# metiumacs2.net
KiCad netlist of a schematic drawn in EAGLE
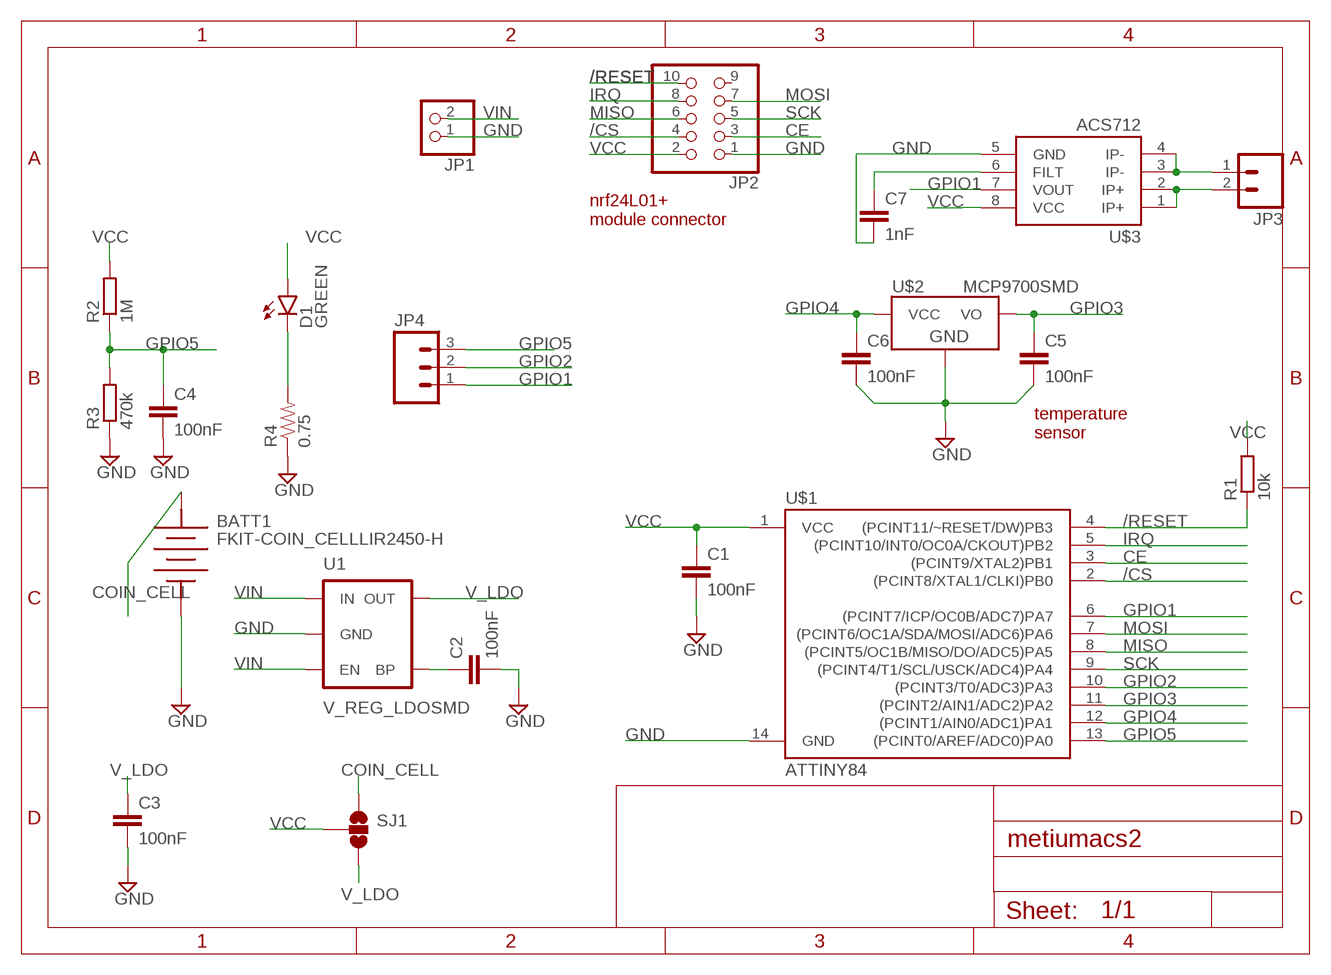
[diagram p0: schematic, sheet 1]

(export (version "E")
  (design (tool "Eeschema 10.0.6"))
  (components
    (comp (ref "BATT1")
      (value "FKIT-COIN_CELLLIR2450-H")
      (footprint "eagle-import:FKIT-LIR2450-H")
      (libsource (lib "eagle-import") (part "FKIT-COIN_CELLLIR2450-H"))
    )
    (comp (ref "C1")
      (value "100nF")
      (footprint "eagle-import:C0805")
      (libsource (lib "eagle-import") (part "C-EUC0805"))
    )
    (comp (ref "C2")
      (value "100nF")
      (footprint "eagle-import:C0805")
      (libsource (lib "eagle-import") (part "C-EUC0805"))
    )
    (comp (ref "C3")
      (value "100nF")
      (footprint "eagle-import:C0805")
      (libsource (lib "eagle-import") (part "C-EUC0805"))
    )
    (comp (ref "C4")
      (value "100nF")
      (footprint "eagle-import:C0805")
      (libsource (lib "eagle-import") (part "C-EUC0805"))
    )
    (comp (ref "C5")
      (value "100nF")
      (footprint "eagle-import:C0805")
      (libsource (lib "eagle-import") (part "C-EUC0805"))
    )
    (comp (ref "C6")
      (value "100nF")
      (footprint "eagle-import:C0805")
      (libsource (lib "eagle-import") (part "C-EUC0805"))
    )
    (comp (ref "C7")
      (value "1nF")
      (footprint "eagle-import:0603-CAP")
      (libsource (lib "eagle-import") (part "1NF/1000PF-50V-10%(0603)"))
    )
    (comp (ref "D1")
      (value "GREEN")
      (footprint "eagle-import:LED-0603")
      (libsource (lib "eagle-import") (part "LED-GREEN0603"))
    )
    (comp (ref "JP1")
      (value "HEADER-1X2ROUND")
      (footprint "eagle-import:1X02_ROUND")
      (libsource (lib "eagle-import") (part "HEADER-1X2ROUND"))
    )
    (comp (ref "JP2")
      (value "PINHD-2X5")
      (footprint "eagle-import:2X05M")
      (libsource (lib "eagle-import") (part "PINHD-2X5"))
    )
    (comp (ref "JP3")
      (value "M02PTH4")
      (footprint "eagle-import:1X02_XTRA_BIG")
      (libsource (lib "eagle-import") (part "M02PTH4"))
    )
    (comp (ref "JP4")
      (value "M03LONGPADS")
      (footprint "eagle-import:1X03_LONGPADS")
      (libsource (lib "eagle-import") (part "M03LONGPADS"))
    )
    (comp (ref "R1")
      (value "10k")
      (footprint "eagle-import:R0805")
      (libsource (lib "eagle-import") (part "R-EU_R0805"))
    )
    (comp (ref "R2")
      (value "1M")
      (footprint "eagle-import:R0805")
      (libsource (lib "eagle-import") (part "R-EU_R0805"))
    )
    (comp (ref "R3")
      (value "470k")
      (footprint "eagle-import:R0805")
      (libsource (lib "eagle-import") (part "R-EU_R0805"))
    )
    (comp (ref "R4")
      (value "0.75")
      (footprint "eagle-import:0805")
      (libsource (lib "eagle-import") (part "0.75OHM-1/4W-1%(0805)"))
    )
    (comp (ref "SJ1")
      (value "SOLDERJUMPER_2WAYS")
      (footprint "eagle-import:SJ_3")
      (libsource (lib "eagle-import") (part "SOLDERJUMPER_2WAYS"))
    )
    (comp (ref "U$1")
      (value "ATTINY84")
      (footprint "eagle-import:SO14")
      (libsource (lib "eagle-import") (part "ATTINY84"))
    )
    (comp (ref "U$2")
      (value "MCP9700SMD")
      (footprint "eagle-import:SOT23-3")
      (libsource (lib "eagle-import") (part "MCP9700SMD"))
    )
    (comp (ref "U$3")
      (value "ACS712")
      (footprint "eagle-import:SO08")
      (libsource (lib "eagle-import") (part "ACS712"))
    )
    (comp (ref "U1")
      (value "V_REG_LDOSMD")
      (footprint "eagle-import:SOT23-5")
      (libsource (lib "eagle-import") (part "V_REG_LDOSMD"))
    )
  )
  (nets
    (net (code "1") (name "/CE") (class "Default")
      (node (ref "JP2") (pin "3") (pinfunction "3_3") (pintype "passive"))
      (node (ref "U$1") (pin "3") (pinfunction "(PCINT9/XTAL2)PB1_3") (pintype "bidirectional"))
    )
    (net (code "2") (name "/COIN_CELL") (class "Default")
      (node (ref "BATT1") (pin "POS") (pinfunction "POS_POS") (pintype "bidirectional"))
      (node (ref "SJ1") (pin "1") (pinfunction "1_1") (pintype "passive"))
    )
    (net (code "3") (name "/GPIO1") (class "Default")
      (node (ref "JP4") (pin "1") (pinfunction "1_1") (pintype "passive"))
      (node (ref "U$1") (pin "6") (pinfunction "(PCINT7/ICP/OC0B/ADC7)PA7_6") (pintype "bidirectional"))
      (node (ref "U$3") (pin "7") (pinfunction "VOUT_7") (pintype "bidirectional"))
    )
    (net (code "4") (name "/GPIO2") (class "Default")
      (node (ref "JP4") (pin "2") (pinfunction "2_2") (pintype "passive"))
      (node (ref "U$1") (pin "10") (pinfunction "(PCINT3/T0/ADC3)PA3_10") (pintype "bidirectional"))
    )
    (net (code "5") (name "/GPIO3") (class "Default")
      (node (ref "C5") (pin "1") (pinfunction "1_1") (pintype "passive"))
      (node (ref "U$1") (pin "11") (pinfunction "(PCINT2/AIN1/ADC2)PA2_11") (pintype "bidirectional"))
      (node (ref "U$2") (pin "2") (pinfunction "VO_2") (pintype "bidirectional"))
    )
    (net (code "6") (name "/GPIO4") (class "Default")
      (node (ref "C6") (pin "1") (pinfunction "1_1") (pintype "passive"))
      (node (ref "U$1") (pin "12") (pinfunction "(PCINT1/AIN0/ADC1)PA1_12") (pintype "bidirectional"))
      (node (ref "U$2") (pin "1") (pinfunction "VCC_1") (pintype "bidirectional"))
    )
    (net (code "7") (name "/GPIO5") (class "Default")
      (node (ref "C4") (pin "1") (pinfunction "1_1") (pintype "passive"))
      (node (ref "JP4") (pin "3") (pinfunction "3_3") (pintype "passive"))
      (node (ref "R2") (pin "1") (pinfunction "1_1") (pintype "passive"))
      (node (ref "R3") (pin "2") (pinfunction "2_2") (pintype "passive"))
      (node (ref "U$1") (pin "13") (pinfunction "(PCINT0/AREF/ADC0)PA0_13") (pintype "bidirectional"))
    )
    (net (code "8") (name "/IRQ") (class "Default")
      (node (ref "JP2") (pin "8") (pinfunction "8_8") (pintype "passive"))
      (node (ref "U$1") (pin "5") (pinfunction "(PCINT10/INT0/OC0A/CKOUT)PB2_5") (pintype "bidirectional"))
    )
    (net (code "9") (name "/MISO") (class "Default")
      (node (ref "JP2") (pin "6") (pinfunction "6_6") (pintype "passive"))
      (node (ref "U$1") (pin "8") (pinfunction "(PCINT5/OC1B/MISO/DO/ADC5)PA5_8") (pintype "bidirectional"))
    )
    (net (code "10") (name "/MOSI") (class "Default")
      (node (ref "JP2") (pin "7") (pinfunction "7_7") (pintype "passive"))
      (node (ref "U$1") (pin "7") (pinfunction "(PCINT6/OC1A/SDA/MOSI/ADC6)PA6_7") (pintype "bidirectional"))
    )
    (net (code "11") (name "/SCK") (class "Default")
      (node (ref "JP2") (pin "5") (pinfunction "5_5") (pintype "passive"))
      (node (ref "U$1") (pin "9") (pinfunction "(PCINT4/T1/SCL/USCK/ADC4)PA4_9") (pintype "bidirectional"))
    )
    (net (code "12") (name "/VCC") (class "Default")
      (node (ref "C1") (pin "1") (pinfunction "1_1") (pintype "passive"))
      (node (ref "D1") (pin "A") (pinfunction "A_A") (pintype "passive"))
      (node (ref "JP2") (pin "2") (pinfunction "2_2") (pintype "passive"))
      (node (ref "R1") (pin "2") (pinfunction "2_2") (pintype "passive"))
      (node (ref "R2") (pin "2") (pinfunction "2_2") (pintype "passive"))
      (node (ref "SJ1") (pin "2") (pinfunction "2_2") (pintype "passive"))
      (node (ref "U$1") (pin "1") (pinfunction "VCC_1") (pintype "bidirectional"))
      (node (ref "U$3") (pin "8") (pinfunction "VCC_8") (pintype "bidirectional"))
    )
    (net (code "13") (name "/VIN") (class "Default")
      (node (ref "JP1") (pin "2") (pinfunction "2_2") (pintype "passive"))
      (node (ref "U1") (pin "1") (pinfunction "IN_1") (pintype "input"))
      (node (ref "U1") (pin "3") (pinfunction "EN_3") (pintype "input"))
    )
    (net (code "14") (name "/V_LDO") (class "Default")
      (node (ref "C3") (pin "1") (pinfunction "1_1") (pintype "passive"))
      (node (ref "SJ1") (pin "3") (pinfunction "3_3") (pintype "passive"))
      (node (ref "U1") (pin "5") (pinfunction "OUT_5") (pintype "passive"))
    )
    (net (code "15") (name "/{slash}CS") (class "Default")
      (node (ref "JP2") (pin "4") (pinfunction "4_4") (pintype "passive"))
      (node (ref "U$1") (pin "2") (pinfunction "(PCINT8/XTAL1/CLKI)PB0_2") (pintype "bidirectional"))
    )
    (net (code "16") (name "/{slash}RESET") (class "Default")
      (node (ref "JP2") (pin "10") (pinfunction "10_10") (pintype "passive"))
      (node (ref "R1") (pin "1") (pinfunction "1_1") (pintype "passive"))
      (node (ref "U$1") (pin "4") (pinfunction "(PCINT11/~{RESET/DW})PB3_4") (pintype "bidirectional"))
    )
    (net (code "17") (name "GND") (class "Default")
      (node (ref "BATT1") (pin "NEG") (pinfunction "NEG_NEG") (pintype "bidirectional"))
      (node (ref "C1") (pin "2") (pinfunction "2_2") (pintype "passive"))
      (node (ref "C2") (pin "2") (pinfunction "2_2") (pintype "passive"))
      (node (ref "C3") (pin "2") (pinfunction "2_2") (pintype "passive"))
      (node (ref "C4") (pin "2") (pinfunction "2_2") (pintype "passive"))
      (node (ref "C5") (pin "2") (pinfunction "2_2") (pintype "passive"))
      (node (ref "C6") (pin "2") (pinfunction "2_2") (pintype "passive"))
      (node (ref "C7") (pin "2") (pinfunction "2_2") (pintype "passive"))
      (node (ref "JP1") (pin "1") (pinfunction "1_1") (pintype "passive"))
      (node (ref "JP2") (pin "1") (pinfunction "1_1") (pintype "passive"))
      (node (ref "R3") (pin "1") (pinfunction "1_1") (pintype "passive"))
      (node (ref "R4") (pin "1") (pinfunction "1_1") (pintype "passive"))
      (node (ref "U$1") (pin "14") (pinfunction "GND_14") (pintype "bidirectional"))
      (node (ref "U$2") (pin "3") (pinfunction "GND_3") (pintype "bidirectional"))
      (node (ref "U$3") (pin "5") (pinfunction "GND_5") (pintype "bidirectional"))
      (node (ref "U1") (pin "2") (pinfunction "GND_2") (pintype "input"))
    )
    (net (code "18") (name "Net-(D1-PadC)") (class "Default")
      (node (ref "D1") (pin "C") (pinfunction "C_C") (pintype "passive"))
      (node (ref "R4") (pin "2") (pinfunction "2_2") (pintype "passive"))
    )
    (net (code "19") (name "Net-(JP3-Pad1)") (class "Default")
      (node (ref "JP3") (pin "1") (pinfunction "1_1") (pintype "passive"))
      (node (ref "U$3") (pin "3") (pinfunction "IP-_3") (pintype "bidirectional"))
      (node (ref "U$3") (pin "4") (pinfunction "IP-_4") (pintype "bidirectional"))
    )
    (net (code "20") (name "Net-(JP3-Pad2)") (class "Default")
      (node (ref "JP3") (pin "2") (pinfunction "2_2") (pintype "passive"))
      (node (ref "U$3") (pin "1") (pinfunction "IP+_1") (pintype "bidirectional"))
      (node (ref "U$3") (pin "2") (pinfunction "IP+_2") (pintype "bidirectional"))
    )
    (net (code "21") (name "Net-(U$3-FILT)") (class "Default")
      (node (ref "C7") (pin "1") (pinfunction "1_1") (pintype "passive"))
      (node (ref "U$3") (pin "6") (pinfunction "FILT_6") (pintype "bidirectional"))
    )
    (net (code "22") (name "Net-(U1-BP)") (class "Default")
      (node (ref "C2") (pin "1") (pinfunction "1_1") (pintype "passive"))
      (node (ref "U1") (pin "4") (pinfunction "BP_4") (pintype "input"))
    )
    (net (code "23") (name "unconnected-(JP2-Pad9)") (class "Default")
      (node (ref "JP2") (pin "9") (pinfunction "9_9") (pintype "passive"))
    )
  )
)
